# ESP32_WITH_FLASHER.net
KiCad netlist of a schematic drawn in Altium Designer
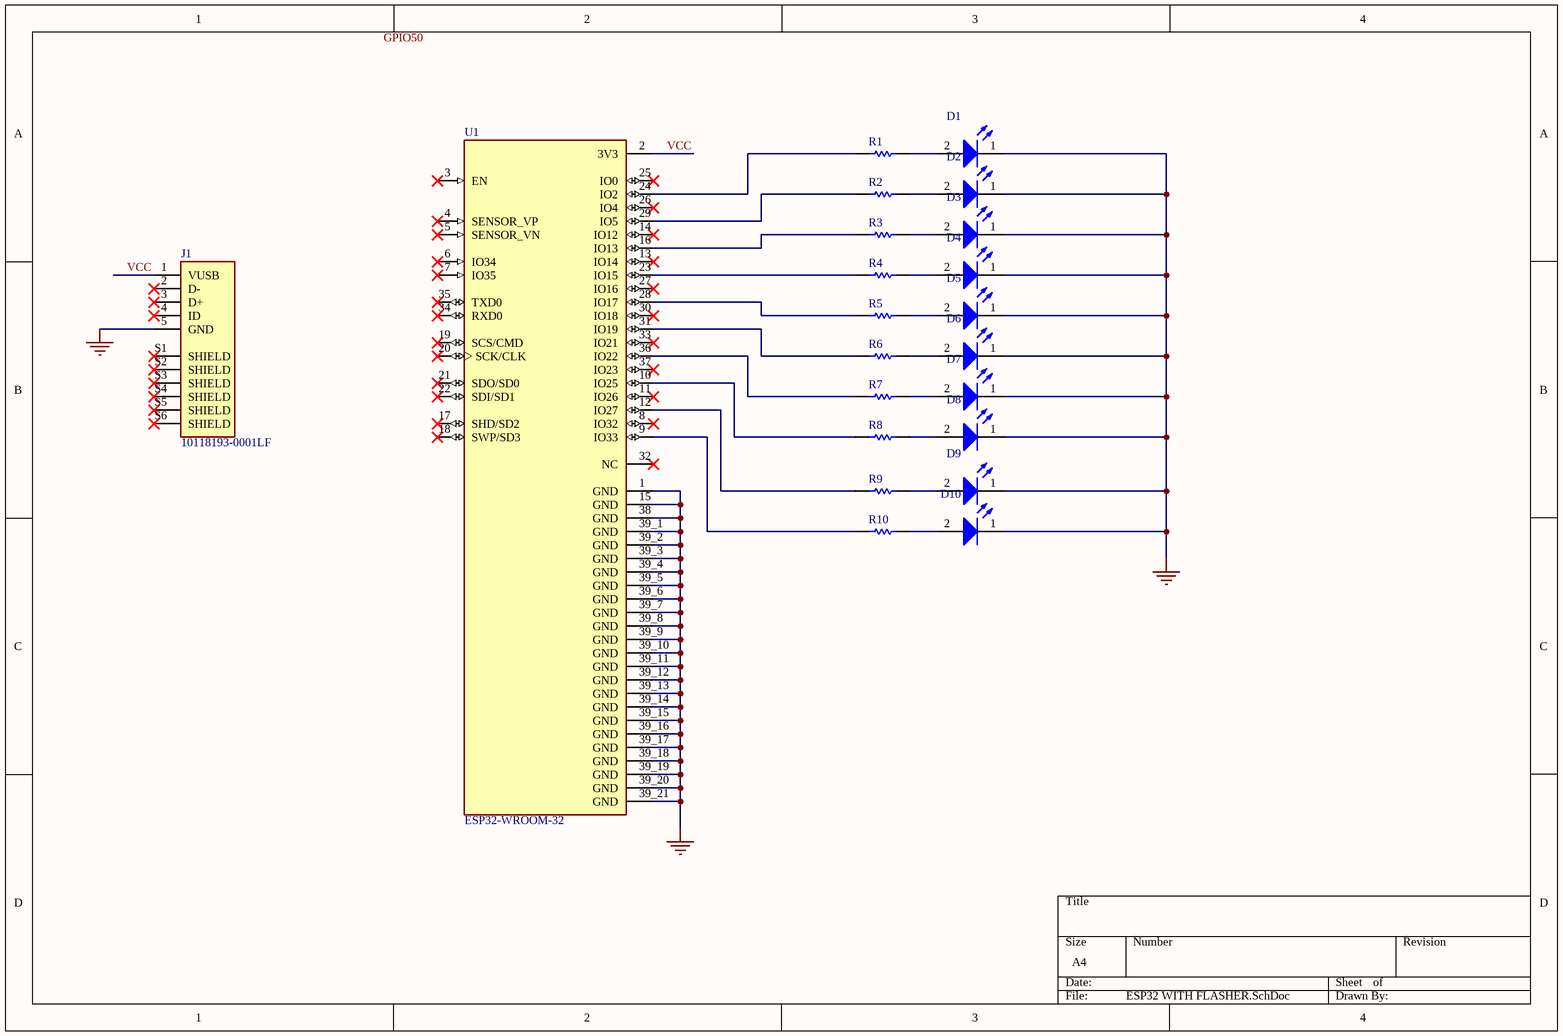
[diagram p0: ESP32 WITH FLASHER.SchDoc]

(export (version "E")
  (design (tool "Eeschema 10.0.6"))
  (components
    (comp (ref "D1")
      (value "15400385A3590")
      (footprint "WL-TIRW_D3.9H5.3")
      (description "15400385A3590 WL-TIRW THT Infrared Round Waterclear")
      (libsource (lib "Altium Content Vault") (part "LED_Infrared_2A-1K"))
    )
    (comp (ref "D2")
      (value "15400385A3590")
      (footprint "WL-TIRW_D3.9H5.3")
      (description "15400385A3590 WL-TIRW THT Infrared Round Waterclear")
      (libsource (lib "Altium Content Vault") (part "LED_Infrared_2A-1K"))
    )
    (comp (ref "D3")
      (value "15400385A3590")
      (footprint "WL-TIRW_D3.9H5.3")
      (description "15400385A3590 WL-TIRW THT Infrared Round Waterclear")
      (libsource (lib "Altium Content Vault") (part "LED_Infrared_2A-1K"))
    )
    (comp (ref "D4")
      (value "15400385A3590")
      (footprint "WL-TIRW_D3.9H5.3")
      (description "15400385A3590 WL-TIRW THT Infrared Round Waterclear")
      (libsource (lib "Altium Content Vault") (part "LED_Infrared_2A-1K"))
    )
    (comp (ref "D5")
      (value "15400385A3590")
      (footprint "WL-TIRW_D3.9H5.3")
      (description "15400385A3590 WL-TIRW THT Infrared Round Waterclear")
      (libsource (lib "Altium Content Vault") (part "LED_Infrared_2A-1K"))
    )
    (comp (ref "D6")
      (value "15400385A3590")
      (footprint "WL-TIRW_D3.9H5.3")
      (description "15400385A3590 WL-TIRW THT Infrared Round Waterclear")
      (libsource (lib "Altium Content Vault") (part "LED_Infrared_2A-1K"))
    )
    (comp (ref "D7")
      (value "15400385A3590")
      (footprint "WL-TIRW_D3.9H5.3")
      (description "15400385A3590 WL-TIRW THT Infrared Round Waterclear")
      (libsource (lib "Altium Content Vault") (part "LED_Infrared_2A-1K"))
    )
    (comp (ref "D8")
      (value "15400385A3590")
      (footprint "WL-TIRW_D3.9H5.3")
      (description "15400385A3590 WL-TIRW THT Infrared Round Waterclear")
      (libsource (lib "Altium Content Vault") (part "LED_Infrared_2A-1K"))
    )
    (comp (ref "D9")
      (value "15400385A3590")
      (footprint "WL-TIRW_D3.9H5.3")
      (description "15400385A3590 WL-TIRW THT Infrared Round Waterclear")
      (libsource (lib "Altium Content Vault") (part "LED_Infrared_2A-1K"))
    )
    (comp (ref "D10")
      (value "15400385A3590")
      (footprint "WL-TIRW_D3.9H5.3")
      (description "15400385A3590 WL-TIRW THT Infrared Round Waterclear")
      (libsource (lib "Altium Content Vault") (part "LED_Infrared_2A-1K"))
    )
    (comp (ref "J1")
      (value "10118193-0001LF")
      (footprint "AMPHENOL_10118193-0001LF")
      (description "Micro USB 2.0, Input Output Connectors, B TYPE RECEPTACLE")
      (fields (field (name "MF") "Amphenol ICC"))
      (libsource (lib "10118193-0001LF") (part "10118193-0001LF"))
    )
    (comp (ref "R1")
      (value "ERJ-8GEY0R00V")
      (footprint "RESC3216X70X50NL05T20")
      (fields (field (name "MANUFACTURER") "Panasonic"))
      (libsource (lib "Altium Content Vault") (part "RES"))
    )
    (comp (ref "R2")
      (value "ERJ-8GEY0R00V")
      (footprint "RESC3216X70X50NL05T20")
      (fields (field (name "MANUFACTURER") "Panasonic"))
      (libsource (lib "Altium Content Vault") (part "RES"))
    )
    (comp (ref "R3")
      (value "ERJ-8GEY0R00V")
      (footprint "RESC3216X70X50NL05T20")
      (fields (field (name "MANUFACTURER") "Panasonic"))
      (libsource (lib "Altium Content Vault") (part "RES"))
    )
    (comp (ref "R4")
      (value "ERJ-8GEY0R00V")
      (footprint "RESC3216X70X50NL05T20")
      (fields (field (name "MANUFACTURER") "Panasonic"))
      (libsource (lib "Altium Content Vault") (part "RES"))
    )
    (comp (ref "R5")
      (value "ERJ-8GEY0R00V")
      (footprint "RESC3216X70X50NL05T20")
      (fields (field (name "MANUFACTURER") "Panasonic"))
      (libsource (lib "Altium Content Vault") (part "RES"))
    )
    (comp (ref "R6")
      (value "ERJ-8GEY0R00V")
      (footprint "RESC3216X70X50NL05T20")
      (fields (field (name "MANUFACTURER") "Panasonic"))
      (libsource (lib "Altium Content Vault") (part "RES"))
    )
    (comp (ref "R7")
      (value "ERJ-8GEY0R00V")
      (footprint "RESC3216X70X50NL05T20")
      (fields (field (name "MANUFACTURER") "Panasonic"))
      (libsource (lib "Altium Content Vault") (part "RES"))
    )
    (comp (ref "R8")
      (value "ERJ-8GEY0R00V")
      (footprint "RESC3216X70X50NL05T20")
      (fields (field (name "MANUFACTURER") "Panasonic"))
      (libsource (lib "Altium Content Vault") (part "RES"))
    )
    (comp (ref "R9")
      (value "ERJ-8GEY0R00V")
      (footprint "RESC3216X70X50NL05T20")
      (fields (field (name "MANUFACTURER") "Panasonic"))
      (libsource (lib "Altium Content Vault") (part "RES"))
    )
    (comp (ref "R10")
      (value "ERJ-8GEY0R00V")
      (footprint "RESC3216X70X50NL05T20")
      (fields (field (name "MANUFACTURER") "Panasonic"))
      (libsource (lib "Altium Content Vault") (part "RES"))
    )
    (comp (ref "U1")
      (value "ESP32-WROOM-32")
      (footprint "MODULE_ESP32-WROOM-32")
      (fields (field (name "MF") "Espressif Systems"))
      (libsource (lib "ESP32-WROOM-32") (part "ESP32-WROOM-32"))
    )
  )
  (nets
    (net (code "2") (name "/VCC") (class "Default")
      (node (ref "J1") (pin "1") (pinfunction "VUSB_1") (pintype "passive"))
      (node (ref "U1") (pin "2") (pinfunction "3V3_2") (pintype "power_in"))
    )
    (net (code "3") (name "GND") (class "Default")
      (node (ref "D1") (pin "1") (pinfunction "K_1") (pintype "passive"))
      (node (ref "D10") (pin "1") (pinfunction "K_1") (pintype "passive"))
      (node (ref "D2") (pin "1") (pinfunction "K_1") (pintype "passive"))
      (node (ref "D3") (pin "1") (pinfunction "K_1") (pintype "passive"))
      (node (ref "D4") (pin "1") (pinfunction "K_1") (pintype "passive"))
      (node (ref "D5") (pin "1") (pinfunction "K_1") (pintype "passive"))
      (node (ref "D6") (pin "1") (pinfunction "K_1") (pintype "passive"))
      (node (ref "D7") (pin "1") (pinfunction "K_1") (pintype "passive"))
      (node (ref "D8") (pin "1") (pinfunction "K_1") (pintype "passive"))
      (node (ref "D9") (pin "1") (pinfunction "K_1") (pintype "passive"))
      (node (ref "J1") (pin "5") (pinfunction "GND_5") (pintype "passive"))
      (node (ref "U1") (pin "1") (pinfunction "GND_1") (pintype "power_in"))
      (node (ref "U1") (pin "15") (pinfunction "GND_15") (pintype "power_in"))
      (node (ref "U1") (pin "38") (pinfunction "GND_38") (pintype "power_in"))
      (node (ref "U1") (pin "39_1") (pinfunction "GND_39_1") (pintype "power_in"))
      (node (ref "U1") (pin "39_10") (pinfunction "GND_39_10") (pintype "power_in"))
      (node (ref "U1") (pin "39_11") (pinfunction "GND_39_11") (pintype "power_in"))
      (node (ref "U1") (pin "39_12") (pinfunction "GND_39_12") (pintype "power_in"))
      (node (ref "U1") (pin "39_13") (pinfunction "GND_39_13") (pintype "power_in"))
      (node (ref "U1") (pin "39_14") (pinfunction "GND_39_14") (pintype "power_in"))
      (node (ref "U1") (pin "39_15") (pinfunction "GND_39_15") (pintype "power_in"))
      (node (ref "U1") (pin "39_16") (pinfunction "GND_39_16") (pintype "power_in"))
      (node (ref "U1") (pin "39_17") (pinfunction "GND_39_17") (pintype "power_in"))
      (node (ref "U1") (pin "39_18") (pinfunction "GND_39_18") (pintype "power_in"))
      (node (ref "U1") (pin "39_19") (pinfunction "GND_39_19") (pintype "power_in"))
      (node (ref "U1") (pin "39_2") (pinfunction "GND_39_2") (pintype "power_in"))
      (node (ref "U1") (pin "39_20") (pinfunction "GND_39_20") (pintype "power_in"))
      (node (ref "U1") (pin "39_21") (pinfunction "GND_39_21") (pintype "power_in"))
      (node (ref "U1") (pin "39_3") (pinfunction "GND_39_3") (pintype "power_in"))
      (node (ref "U1") (pin "39_4") (pinfunction "GND_39_4") (pintype "power_in"))
      (node (ref "U1") (pin "39_5") (pinfunction "GND_39_5") (pintype "power_in"))
      (node (ref "U1") (pin "39_6") (pinfunction "GND_39_6") (pintype "power_in"))
      (node (ref "U1") (pin "39_7") (pinfunction "GND_39_7") (pintype "power_in"))
      (node (ref "U1") (pin "39_8") (pinfunction "GND_39_8") (pintype "power_in"))
      (node (ref "U1") (pin "39_9") (pinfunction "GND_39_9") (pintype "power_in"))
    )
    (net (code "4") (name "Net-(D1-A)") (class "Default")
      (node (ref "D1") (pin "2") (pinfunction "A_2") (pintype "passive"))
      (node (ref "R1") (pin "2") (pinfunction "2_2") (pintype "passive"))
    )
    (net (code "5") (name "Net-(D2-A)") (class "Default")
      (node (ref "D2") (pin "2") (pinfunction "A_2") (pintype "passive"))
      (node (ref "R2") (pin "2") (pinfunction "2_2") (pintype "passive"))
    )
    (net (code "6") (name "Net-(D3-A)") (class "Default")
      (node (ref "D3") (pin "2") (pinfunction "A_2") (pintype "passive"))
      (node (ref "R3") (pin "2") (pinfunction "2_2") (pintype "passive"))
    )
    (net (code "7") (name "Net-(D4-A)") (class "Default")
      (node (ref "D4") (pin "2") (pinfunction "A_2") (pintype "passive"))
      (node (ref "R4") (pin "2") (pinfunction "2_2") (pintype "passive"))
    )
    (net (code "8") (name "Net-(D5-A)") (class "Default")
      (node (ref "D5") (pin "2") (pinfunction "A_2") (pintype "passive"))
      (node (ref "R5") (pin "2") (pinfunction "2_2") (pintype "passive"))
    )
    (net (code "9") (name "Net-(D6-A)") (class "Default")
      (node (ref "D6") (pin "2") (pinfunction "A_2") (pintype "passive"))
      (node (ref "R6") (pin "2") (pinfunction "2_2") (pintype "passive"))
    )
    (net (code "10") (name "Net-(D7-A)") (class "Default")
      (node (ref "D7") (pin "2") (pinfunction "A_2") (pintype "passive"))
      (node (ref "R7") (pin "2") (pinfunction "2_2") (pintype "passive"))
    )
    (net (code "11") (name "Net-(D8-A)") (class "Default")
      (node (ref "D8") (pin "2") (pinfunction "A_2") (pintype "passive"))
      (node (ref "R8") (pin "2") (pinfunction "2_2") (pintype "passive"))
    )
    (net (code "12") (name "Net-(D9-A)") (class "Default")
      (node (ref "D9") (pin "2") (pinfunction "A_2") (pintype "passive"))
      (node (ref "R9") (pin "2") (pinfunction "2_2") (pintype "passive"))
    )
    (net (code "13") (name "Net-(D10-A)") (class "Default")
      (node (ref "D10") (pin "2") (pinfunction "A_2") (pintype "passive"))
      (node (ref "R10") (pin "2") (pinfunction "2_2") (pintype "passive"))
    )
    (net (code "14") (name "Net-(U1-IO2)") (class "Default")
      (node (ref "R1") (pin "1") (pinfunction "1_1") (pintype "passive"))
      (node (ref "U1") (pin "24") (pinfunction "IO2_24") (pintype "bidirectional"))
    )
    (net (code "15") (name "Net-(U1-IO5)") (class "Default")
      (node (ref "R2") (pin "1") (pinfunction "1_1") (pintype "passive"))
      (node (ref "U1") (pin "29") (pinfunction "IO5_29") (pintype "bidirectional"))
    )
    (net (code "16") (name "Net-(U1-IO13)") (class "Default")
      (node (ref "R3") (pin "1") (pinfunction "1_1") (pintype "passive"))
      (node (ref "U1") (pin "16") (pinfunction "IO13_16") (pintype "bidirectional"))
    )
    (net (code "17") (name "Net-(U1-IO15)") (class "Default")
      (node (ref "R4") (pin "1") (pinfunction "1_1") (pintype "passive"))
      (node (ref "U1") (pin "23") (pinfunction "IO15_23") (pintype "bidirectional"))
    )
    (net (code "18") (name "Net-(U1-IO17)") (class "Default")
      (node (ref "R5") (pin "1") (pinfunction "1_1") (pintype "passive"))
      (node (ref "U1") (pin "28") (pinfunction "IO17_28") (pintype "bidirectional"))
    )
    (net (code "19") (name "Net-(U1-IO19)") (class "Default")
      (node (ref "R6") (pin "1") (pinfunction "1_1") (pintype "passive"))
      (node (ref "U1") (pin "31") (pinfunction "IO19_31") (pintype "bidirectional"))
    )
    (net (code "20") (name "Net-(U1-IO22)") (class "Default")
      (node (ref "R7") (pin "1") (pinfunction "1_1") (pintype "passive"))
      (node (ref "U1") (pin "36") (pinfunction "IO22_36") (pintype "bidirectional"))
    )
    (net (code "21") (name "Net-(U1-IO25)") (class "Default")
      (node (ref "R8") (pin "1") (pinfunction "1_1") (pintype "passive"))
      (node (ref "U1") (pin "10") (pinfunction "IO25_10") (pintype "bidirectional"))
    )
    (net (code "22") (name "Net-(U1-IO27)") (class "Default")
      (node (ref "R9") (pin "1") (pinfunction "1_1") (pintype "passive"))
      (node (ref "U1") (pin "12") (pinfunction "IO27_12") (pintype "bidirectional"))
    )
    (net (code "23") (name "Net-(U1-IO33)") (class "Default")
      (node (ref "R10") (pin "1") (pinfunction "1_1") (pintype "passive"))
      (node (ref "U1") (pin "9") (pinfunction "IO33_9") (pintype "bidirectional"))
    )
    (net (code "24") (name "unconnected-(J1-D+-Pad3)") (class "Default")
      (node (ref "J1") (pin "3") (pinfunction "D+_3") (pintype "passive+no_connect"))
    )
    (net (code "25") (name "unconnected-(J1-D--Pad2)") (class "Default")
      (node (ref "J1") (pin "2") (pinfunction "D-_2") (pintype "passive+no_connect"))
    )
    (net (code "26") (name "unconnected-(J1-ID-Pad4)") (class "Default")
      (node (ref "J1") (pin "4") (pinfunction "ID_4") (pintype "passive+no_connect"))
    )
    (net (code "27") (name "unconnected-(J1-SHIELD-PadS1)") (class "Default")
      (node (ref "J1") (pin "S1") (pinfunction "SHIELD_S1") (pintype "passive+no_connect"))
    )
    (net (code "28") (name "unconnected-(J1-SHIELD-PadS2)") (class "Default")
      (node (ref "J1") (pin "S2") (pinfunction "SHIELD_S2") (pintype "passive+no_connect"))
    )
    (net (code "29") (name "unconnected-(J1-SHIELD-PadS3)") (class "Default")
      (node (ref "J1") (pin "S3") (pinfunction "SHIELD_S3") (pintype "passive+no_connect"))
    )
    (net (code "30") (name "unconnected-(J1-SHIELD-PadS4)") (class "Default")
      (node (ref "J1") (pin "S4") (pinfunction "SHIELD_S4") (pintype "passive+no_connect"))
    )
    (net (code "31") (name "unconnected-(J1-SHIELD-PadS5)") (class "Default")
      (node (ref "J1") (pin "S5") (pinfunction "SHIELD_S5") (pintype "passive+no_connect"))
    )
    (net (code "32") (name "unconnected-(J1-SHIELD-PadS6)") (class "Default")
      (node (ref "J1") (pin "S6") (pinfunction "SHIELD_S6") (pintype "passive+no_connect"))
    )
    (net (code "33") (name "unconnected-(U1-EN-Pad3)") (class "Default")
      (node (ref "U1") (pin "3") (pinfunction "EN_3") (pintype "input+no_connect"))
    )
    (net (code "34") (name "unconnected-(U1-IO0-Pad25)") (class "Default")
      (node (ref "U1") (pin "25") (pinfunction "IO0_25") (pintype "bidirectional+no_connect"))
    )
    (net (code "35") (name "unconnected-(U1-IO4-Pad26)") (class "Default")
      (node (ref "U1") (pin "26") (pinfunction "IO4_26") (pintype "bidirectional+no_connect"))
    )
    (net (code "36") (name "unconnected-(U1-IO12-Pad14)") (class "Default")
      (node (ref "U1") (pin "14") (pinfunction "IO12_14") (pintype "bidirectional+no_connect"))
    )
    (net (code "37") (name "unconnected-(U1-IO14-Pad13)") (class "Default")
      (node (ref "U1") (pin "13") (pinfunction "IO14_13") (pintype "bidirectional+no_connect"))
    )
    (net (code "38") (name "unconnected-(U1-IO16-Pad27)") (class "Default")
      (node (ref "U1") (pin "27") (pinfunction "IO16_27") (pintype "bidirectional+no_connect"))
    )
    (net (code "39") (name "unconnected-(U1-IO18-Pad30)") (class "Default")
      (node (ref "U1") (pin "30") (pinfunction "IO18_30") (pintype "bidirectional+no_connect"))
    )
    (net (code "40") (name "unconnected-(U1-IO21-Pad33)") (class "Default")
      (node (ref "U1") (pin "33") (pinfunction "IO21_33") (pintype "bidirectional+no_connect"))
    )
    (net (code "41") (name "unconnected-(U1-IO23-Pad37)") (class "Default")
      (node (ref "U1") (pin "37") (pinfunction "IO23_37") (pintype "bidirectional+no_connect"))
    )
    (net (code "42") (name "unconnected-(U1-IO26-Pad11)") (class "Default")
      (node (ref "U1") (pin "11") (pinfunction "IO26_11") (pintype "bidirectional+no_connect"))
    )
    (net (code "43") (name "unconnected-(U1-IO32-Pad8)") (class "Default")
      (node (ref "U1") (pin "8") (pinfunction "IO32_8") (pintype "bidirectional+no_connect"))
    )
    (net (code "44") (name "unconnected-(U1-IO34-Pad6)") (class "Default")
      (node (ref "U1") (pin "6") (pinfunction "IO34_6") (pintype "input+no_connect"))
    )
    (net (code "45") (name "unconnected-(U1-IO35-Pad7)") (class "Default")
      (node (ref "U1") (pin "7") (pinfunction "IO35_7") (pintype "input+no_connect"))
    )
    (net (code "46") (name "unconnected-(U1-NC-Pad32)") (class "Default")
      (node (ref "U1") (pin "32") (pinfunction "NC_32") (pintype "passive+no_connect"))
    )
    (net (code "47") (name "unconnected-(U1-RXD0-Pad34)") (class "Default")
      (node (ref "U1") (pin "34") (pinfunction "RXD0_34") (pintype "bidirectional+no_connect"))
    )
    (net (code "48") (name "unconnected-(U1-SCK{slash}CLK-Pad20)") (class "Default")
      (node (ref "U1") (pin "20") (pinfunction "SCK/CLK_20") (pintype "bidirectional+no_connect"))
    )
    (net (code "49") (name "unconnected-(U1-SCS{slash}CMD-Pad19)") (class "Default")
      (node (ref "U1") (pin "19") (pinfunction "SCS/CMD_19") (pintype "bidirectional+no_connect"))
    )
    (net (code "50") (name "unconnected-(U1-SDI{slash}SD1-Pad22)") (class "Default")
      (node (ref "U1") (pin "22") (pinfunction "SDI/SD1_22") (pintype "bidirectional+no_connect"))
    )
    (net (code "51") (name "unconnected-(U1-SDO{slash}SD0-Pad21)") (class "Default")
      (node (ref "U1") (pin "21") (pinfunction "SDO/SD0_21") (pintype "bidirectional+no_connect"))
    )
    (net (code "52") (name "unconnected-(U1-SENSOR_VN-Pad5)") (class "Default")
      (node (ref "U1") (pin "5") (pinfunction "SENSOR_VN_5") (pintype "input+no_connect"))
    )
    (net (code "53") (name "unconnected-(U1-SENSOR_VP-Pad4)") (class "Default")
      (node (ref "U1") (pin "4") (pinfunction "SENSOR_VP_4") (pintype "input+no_connect"))
    )
    (net (code "54") (name "unconnected-(U1-SHD{slash}SD2-Pad17)") (class "Default")
      (node (ref "U1") (pin "17") (pinfunction "SHD/SD2_17") (pintype "bidirectional+no_connect"))
    )
    (net (code "55") (name "unconnected-(U1-SWP{slash}SD3-Pad18)") (class "Default")
      (node (ref "U1") (pin "18") (pinfunction "SWP/SD3_18") (pintype "bidirectional+no_connect"))
    )
    (net (code "56") (name "unconnected-(U1-TXD0-Pad35)") (class "Default")
      (node (ref "U1") (pin "35") (pinfunction "TXD0_35") (pintype "bidirectional+no_connect"))
    )
  )
)
